# drvinput3.net
KiCad netlist of a schematic drawn in Altium Designer
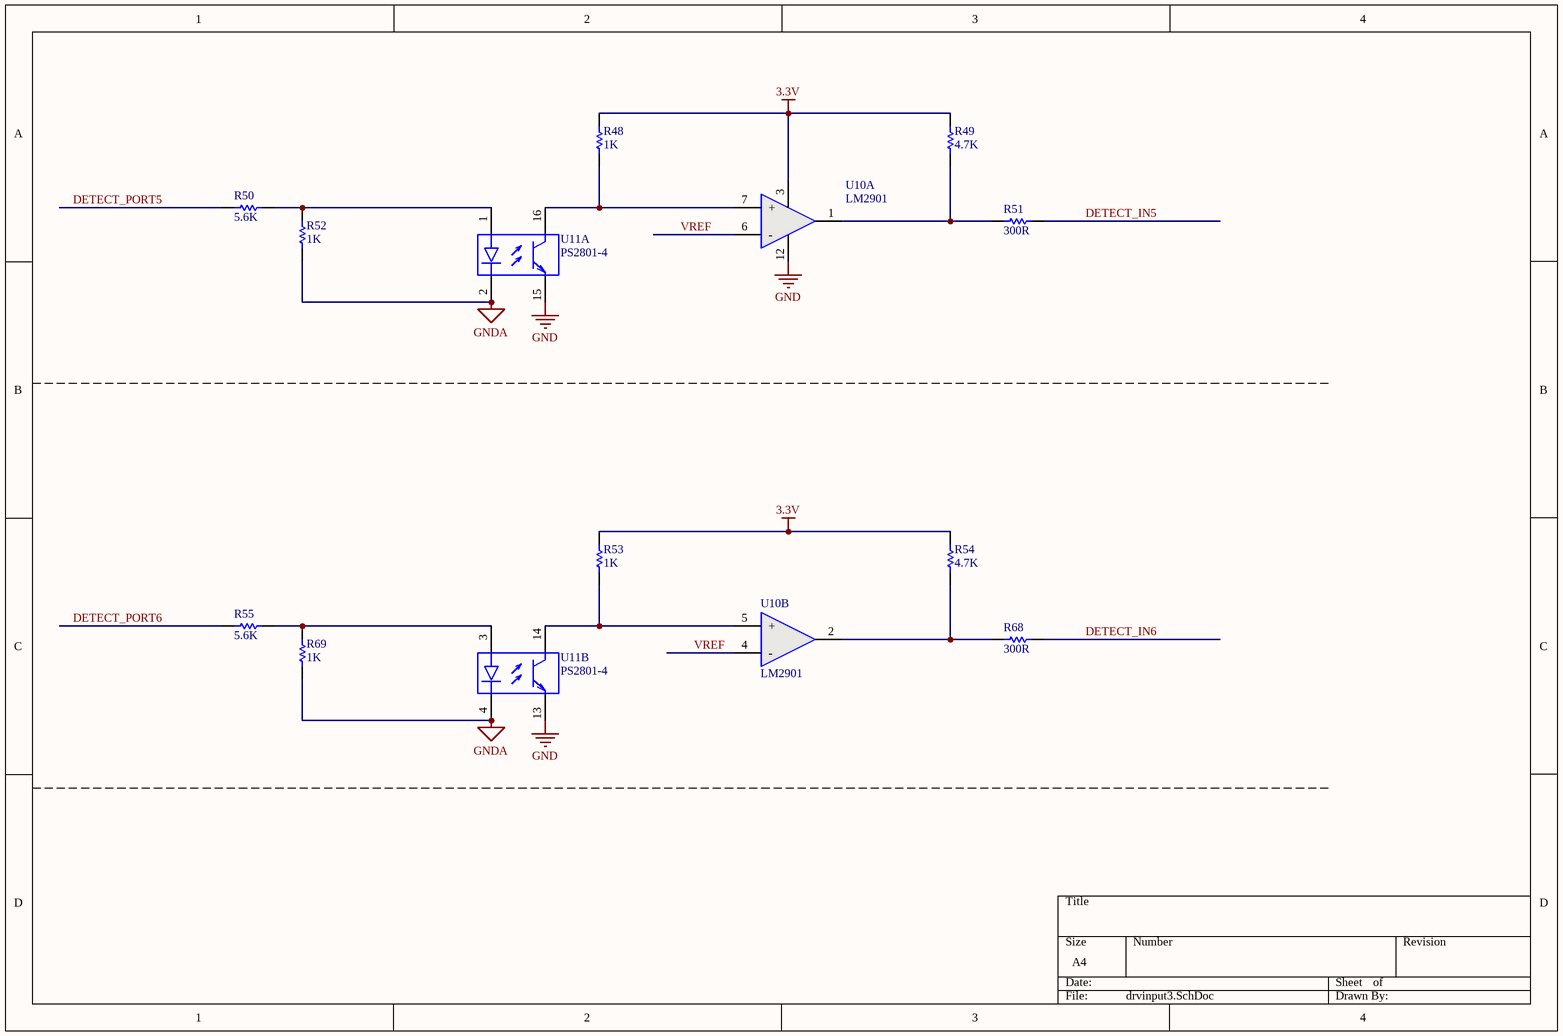
[diagram p0: drvinput3.SchDoc]

(export (version "E")
  (design (tool "Eeschema 10.0.6"))
  (components
    (comp (ref "R48")
      (value "1K")
      (footprint "RESC2012M")
      (description "Resistor")
      (fields (field (name "PUBLISHER") "Altium Limited"))
      (libsource (lib "Miscellaneous Devices") (part "Res1"))
    )
    (comp (ref "R49")
      (value "4.7K")
      (footprint "RESC2012M")
      (description "Resistor")
      (fields (field (name "PUBLISHER") "Altium Limited"))
      (libsource (lib "Miscellaneous Devices") (part "Res1"))
    )
    (comp (ref "R50")
      (value "5.6K")
      (footprint "RESC2012M")
      (description "Resistor")
      (fields (field (name "PUBLISHER") "Altium Limited"))
      (libsource (lib "Miscellaneous Devices") (part "Res1"))
    )
    (comp (ref "R51")
      (value "300R")
      (footprint "RESC2012M")
      (description "Resistor")
      (fields (field (name "PUBLISHER") "Altium Limited"))
      (libsource (lib "Miscellaneous Devices") (part "Res1"))
    )
    (comp (ref "R52")
      (value "1K")
      (footprint "RESC2012M")
      (description "Resistor")
      (fields (field (name "PUBLISHER") "Altium Limited"))
      (libsource (lib "Miscellaneous Devices") (part "Res1"))
    )
    (comp (ref "R53")
      (value "1K")
      (footprint "RESC2012M")
      (description "Resistor")
      (fields (field (name "PUBLISHER") "Altium Limited"))
      (libsource (lib "Miscellaneous Devices") (part "Res1"))
    )
    (comp (ref "R54")
      (value "4.7K")
      (footprint "RESC2012M")
      (description "Resistor")
      (fields (field (name "PUBLISHER") "Altium Limited"))
      (libsource (lib "Miscellaneous Devices") (part "Res1"))
    )
    (comp (ref "R55")
      (value "5.6K")
      (footprint "RESC2012M")
      (description "Resistor")
      (fields (field (name "PUBLISHER") "Altium Limited"))
      (libsource (lib "Miscellaneous Devices") (part "Res1"))
    )
    (comp (ref "R68")
      (value "300R")
      (footprint "RESC2012M")
      (description "Resistor")
      (fields (field (name "PUBLISHER") "Altium Limited"))
      (libsource (lib "Miscellaneous Devices") (part "Res1"))
    )
    (comp (ref "R69")
      (value "1K")
      (footprint "RESC2012M")
      (description "Resistor")
      (fields (field (name "PUBLISHER") "Altium Limited"))
      (libsource (lib "Miscellaneous Devices") (part "Res1"))
    )
    (comp (ref "U10")
      (value "LM2901")
      (footprint "SOIC-14AM")
      (description "4通道差分比较器芯片")
      (libsource (lib "UserSchDev") (part "LM2901"))
    )
    (comp (ref "U11")
      (value "PS2801-4")
      (footprint "SOIC16_N")
      (fields (field (name "PUBLISHER") "Altium Limited"))
      (libsource (lib "UserSchDev") (part "PS2801-4"))
    )
  )
  (nets
    (net (code "1") (name "/DETECT_IN5") (class "Default")
      (node (ref "R51") (pin "1") (pinfunction "1_1") (pintype "passive"))
    )
    (net (code "2") (name "/DETECT_IN6") (class "Default")
      (node (ref "R68") (pin "2") (pinfunction "2_2") (pintype "passive"))
    )
    (net (code "3") (name "/DETECT_PORT5") (class "Default")
      (node (ref "R50") (pin "2") (pinfunction "2_2") (pintype "passive"))
    )
    (net (code "4") (name "/DETECT_PORT6") (class "Default")
      (node (ref "R55") (pin "2") (pinfunction "2_2") (pintype "passive"))
    )
    (net (code "5") (name "/VREF") (class "Default")
      (node (ref "U10") (pin "4") (pinfunction "-_4") (pintype "passive"))
      (node (ref "U10") (pin "6") (pinfunction "-_6") (pintype "passive"))
    )
    (net (code "6") (name "3.3V") (class "Default")
      (node (ref "R48") (pin "1") (pinfunction "1_1") (pintype "passive"))
      (node (ref "R49") (pin "2") (pinfunction "2_2") (pintype "passive"))
      (node (ref "R53") (pin "1") (pinfunction "1_1") (pintype "passive"))
      (node (ref "R54") (pin "2") (pinfunction "2_2") (pintype "passive"))
      (node (ref "U10") (pin "3") (pinfunction "V+_3") (pintype "power_in"))
    )
    (net (code "7") (name "GND") (class "Default")
      (node (ref "U10") (pin "12") (pinfunction "V-_12") (pintype "power_in"))
      (node (ref "U11") (pin "13") (pinfunction "E_13") (pintype "passive"))
      (node (ref "U11") (pin "15") (pinfunction "E_15") (pintype "passive"))
    )
    (net (code "8") (name "GNDA") (class "Default")
      (node (ref "R52") (pin "1") (pinfunction "1_1") (pintype "passive"))
      (node (ref "R69") (pin "1") (pinfunction "1_1") (pintype "passive"))
      (node (ref "U11") (pin "2") (pinfunction "-_2") (pintype "passive"))
      (node (ref "U11") (pin "4") (pinfunction "-_4") (pintype "passive"))
    )
    (net (code "9") (name "Net-(U10A-+)") (class "Default")
      (node (ref "R48") (pin "2") (pinfunction "2_2") (pintype "passive"))
      (node (ref "U10") (pin "7") (pinfunction "+_7") (pintype "passive"))
      (node (ref "U11") (pin "16") (pinfunction "C_16") (pintype "passive"))
    )
    (net (code "10") (name "Net-(U10A-OUT)") (class "Default")
      (node (ref "R49") (pin "1") (pinfunction "1_1") (pintype "passive"))
      (node (ref "R51") (pin "2") (pinfunction "2_2") (pintype "passive"))
      (node (ref "U10") (pin "1") (pinfunction "OUT_1") (pintype "passive"))
    )
    (net (code "11") (name "Net-(U10B-+)") (class "Default")
      (node (ref "R53") (pin "2") (pinfunction "2_2") (pintype "passive"))
      (node (ref "U10") (pin "5") (pinfunction "+_5") (pintype "passive"))
      (node (ref "U11") (pin "14") (pinfunction "C_14") (pintype "passive"))
    )
    (net (code "12") (name "Net-(U10B-OUT)") (class "Default")
      (node (ref "R54") (pin "1") (pinfunction "1_1") (pintype "passive"))
      (node (ref "R68") (pin "1") (pinfunction "1_1") (pintype "passive"))
      (node (ref "U10") (pin "2") (pinfunction "OUT_2") (pintype "passive"))
    )
    (net (code "13") (name "Net-(U11A-+)") (class "Default")
      (node (ref "R50") (pin "1") (pinfunction "1_1") (pintype "passive"))
      (node (ref "R52") (pin "2") (pinfunction "2_2") (pintype "passive"))
      (node (ref "U11") (pin "1") (pinfunction "+_1") (pintype "passive"))
    )
    (net (code "14") (name "Net-(U11B-+)") (class "Default")
      (node (ref "R55") (pin "1") (pinfunction "1_1") (pintype "passive"))
      (node (ref "R69") (pin "2") (pinfunction "2_2") (pintype "passive"))
      (node (ref "U11") (pin "3") (pinfunction "+_3") (pintype "passive"))
    )
  )
)
